# Tacho_StdTeile_panel.net
KiCad netlist of a schematic drawn in EAGLE
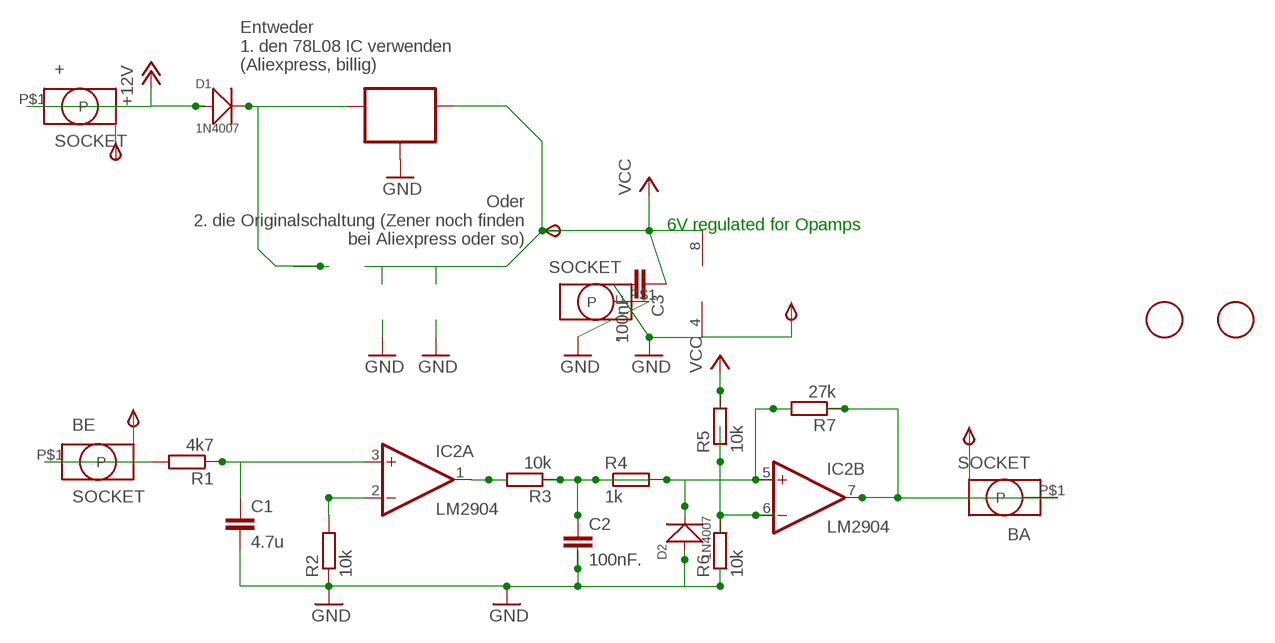
[diagram p0: schematic, sheet 1]
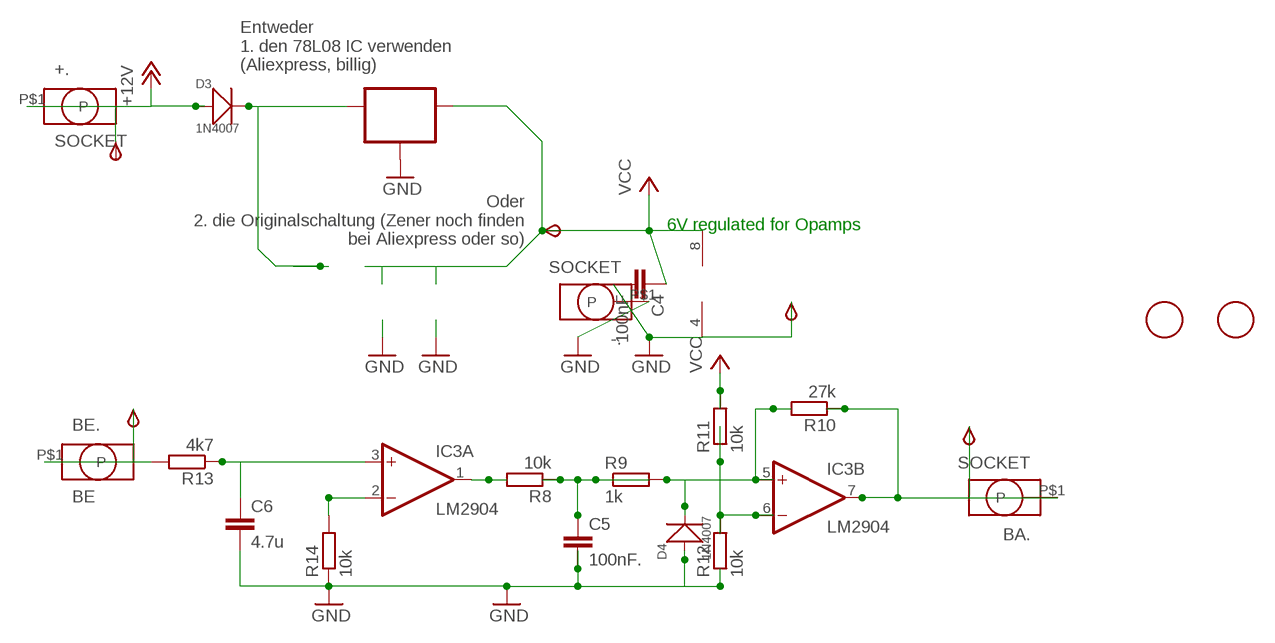
[diagram p1: schematic, sheet 2]
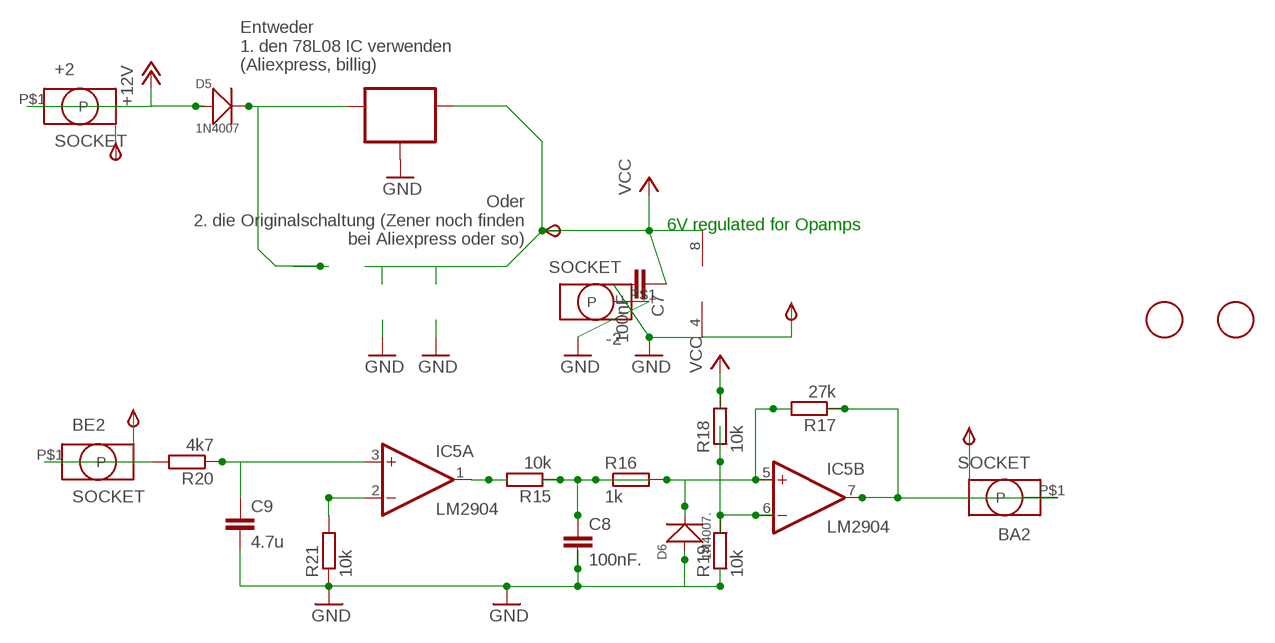
[diagram p2: schematic, sheet 3]
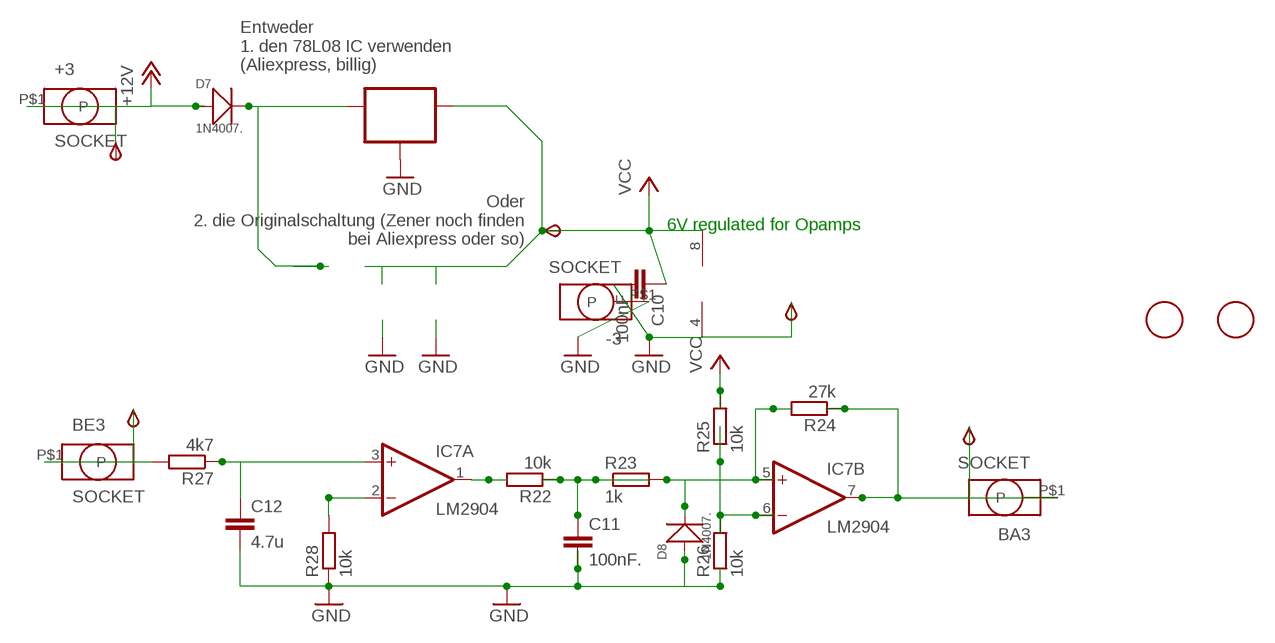
[diagram p3: schematic, sheet 4]
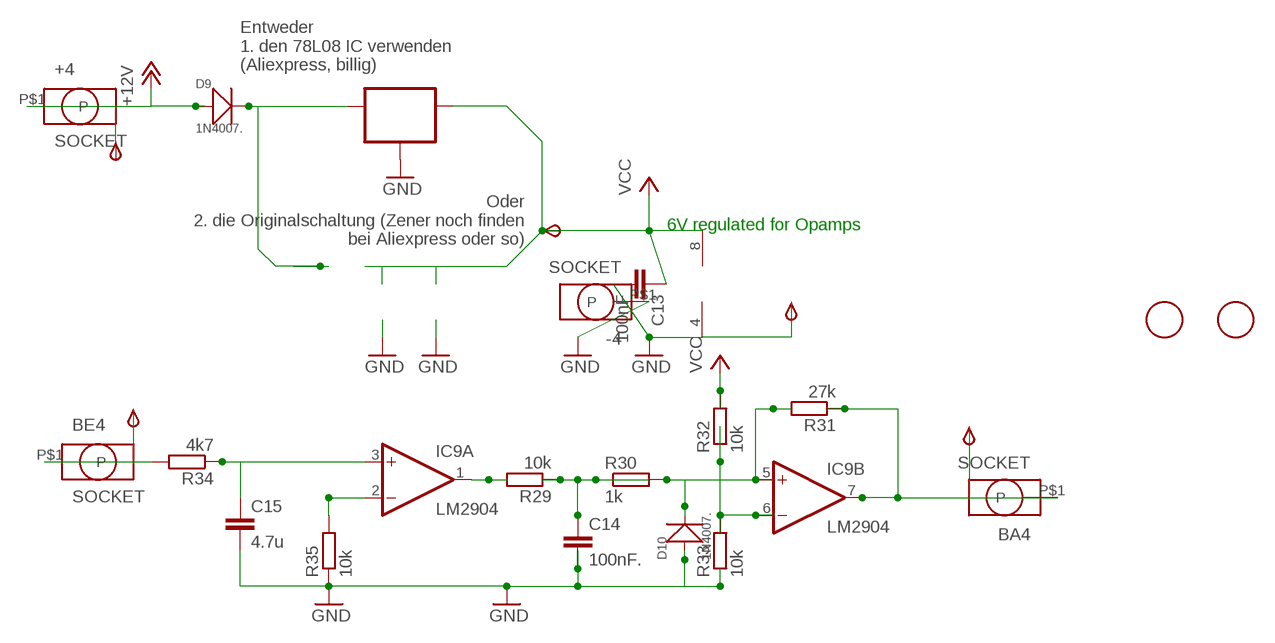
[diagram p4: schematic, sheet 5]
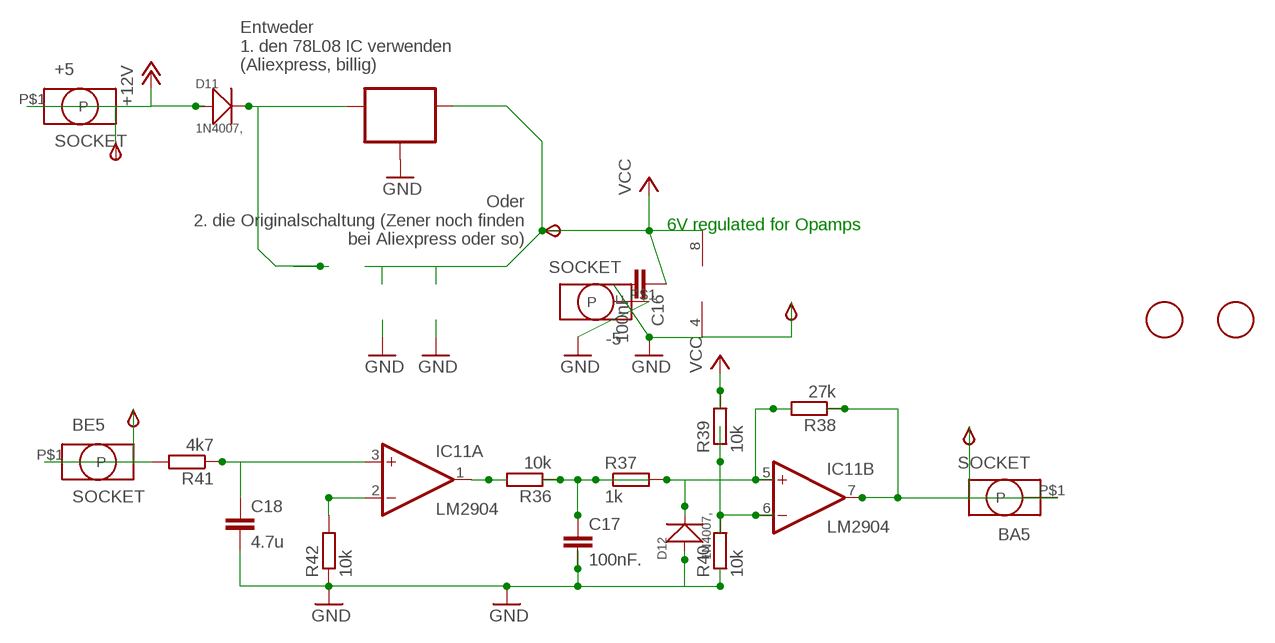
[diagram p5: schematic, sheet 6]
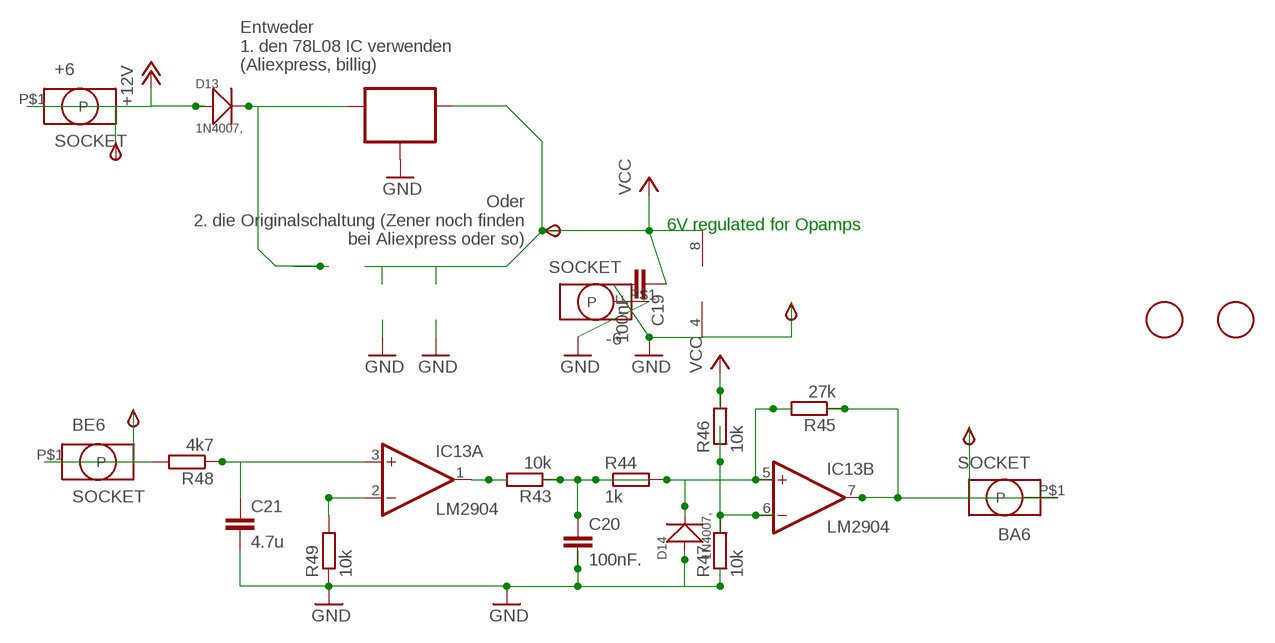
[diagram p6: schematic, sheet 7]
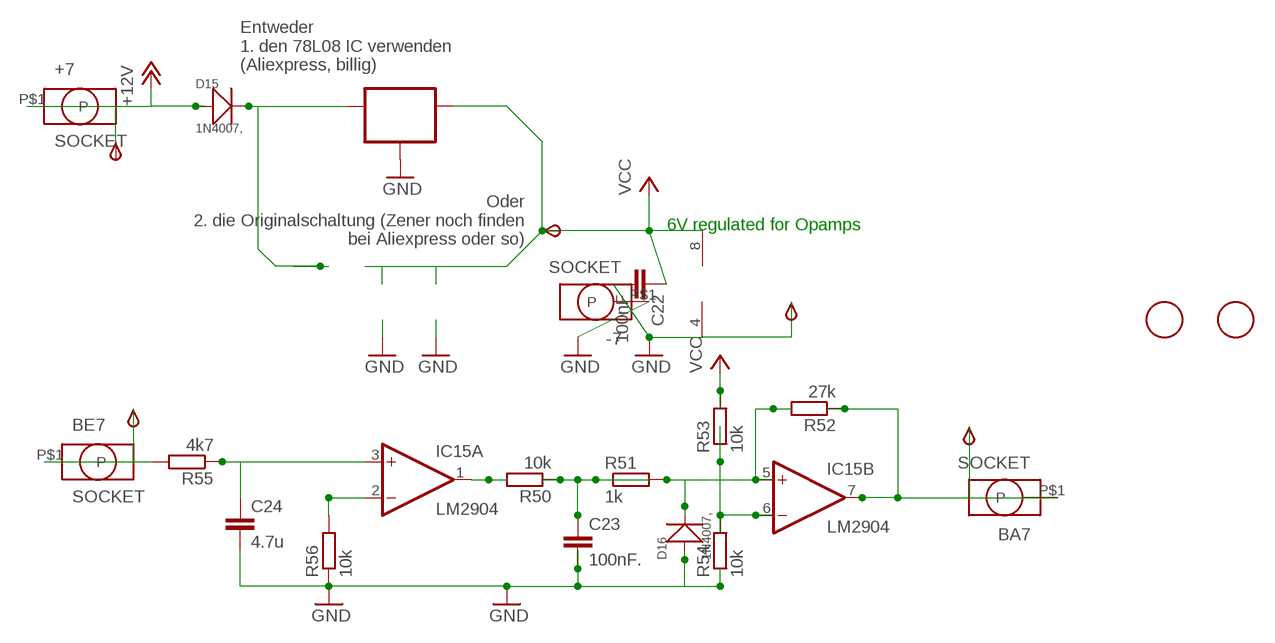
[diagram p7: schematic, sheet 8]

(export (version "E")
  (design (tool "Eeschema 10.0.6"))
  (components
    (comp (ref "+6")
      (value "SOCKET")
      (footprint "eagle-import:ID2.5MM")
      (libsource (lib "eagle-import") (part "SOCKET"))
    )
    (comp (ref "+12V6")
      (value "TPSB2.0")
      (footprint "eagle-import:B2.0")
      (libsource (lib "eagle-import") (part "TPSB2.0"))
    )
    (comp (ref "-6")
      (value "SOCKET")
      (footprint "eagle-import:ID2.5MM")
      (libsource (lib "eagle-import") (part "SOCKET"))
    )
    (comp (ref "6V6")
      (value "TPSB2.0")
      (footprint "eagle-import:B2.0")
      (libsource (lib "eagle-import") (part "TPSB2.0"))
    )
    (comp (ref "AUS6")
      (value "TPSB2.0")
      (footprint "eagle-import:B2.0")
      (libsource (lib "eagle-import") (part "TPSB2.0"))
    )
    (comp (ref "BA6")
      (value "SOCKET")
      (footprint "eagle-import:ID2.5MM")
      (libsource (lib "eagle-import") (part "SOCKET"))
    )
    (comp (ref "BE6")
      (value "SOCKET")
      (footprint "eagle-import:ID2.5MM")
      (libsource (lib "eagle-import") (part "SOCKET"))
    )
    (comp (ref "C19")
      (value "100nF")
      (footprint "eagle-import:C0805K")
      (libsource (lib "eagle-import") (part "C-EUC0805K"))
    )
    (comp (ref "C20")
      (value "100nF.")
      (footprint "eagle-import:C0805K")
      (libsource (lib "eagle-import") (part "C-EUC0805K"))
    )
    (comp (ref "C21")
      (value "4.7u")
      (footprint "eagle-import:C0805K")
      (libsource (lib "eagle-import") (part "C-EUC0805K"))
    )
    (comp (ref "D13")
      (value "1N4007,")
      (footprint "eagle-import:DO-214AC")
      (fields (field (name "MPN") "1N4007"))
      (libsource (lib "eagle-import") (part "DIODE-GEN-PURPOSE-1KV-1A(DO-214AC)"))
    )
    (comp (ref "D14")
      (value "1N4007,")
      (footprint "eagle-import:DO-214AC")
      (fields (field (name "MPN") "1N4007"))
      (libsource (lib "eagle-import") (part "DIODE-GEN-PURPOSE-1KV-1A(DO-214AC)"))
    )
    (comp (ref "EIN6")
      (value "TPSB2.0")
      (footprint "eagle-import:B2.0")
      (libsource (lib "eagle-import") (part "TPSB2.0"))
    )
    (comp (ref "FID13")
      (value "FIDUCIAL")
      (footprint "eagle-import:FIDUCIAL_1MM")
      (libsource (lib "eagle-import") (part "FIDUCIAL"))
    )
    (comp (ref "FID14")
      (value "FIDUCIAL")
      (footprint "eagle-import:FIDUCIAL_1MM")
      (libsource (lib "eagle-import") (part "FIDUCIAL"))
    )
    (comp (ref "GND55")
      (value "TPSB2.0")
      (footprint "eagle-import:B2.0")
      (libsource (lib "eagle-import") (part "TPSB2.0"))
    )
    (comp (ref "IC13")
      (value "LM2904")
      (footprint "eagle-import:SO08")
      (libsource (lib "eagle-import") (part "LM358D"))
    )
    (comp (ref "IC14")
      (value "78L06")
      (footprint "eagle-import:SOT89_ROUND")
      (libsource (lib "eagle-import") (part "78LXXSOT89_ROUND"))
    )
    (comp (ref "R43")
      (value "10k")
      (footprint "eagle-import:R0805")
      (libsource (lib "eagle-import") (part "R-EU_R0805"))
    )
    (comp (ref "R44")
      (value "1k")
      (footprint "eagle-import:R0805")
      (libsource (lib "eagle-import") (part "R-EU_R0805"))
    )
    (comp (ref "R45")
      (value "27k")
      (footprint "eagle-import:R0805")
      (libsource (lib "eagle-import") (part "R-EU_R0805"))
    )
    (comp (ref "R46")
      (value "10k")
      (footprint "eagle-import:R0805")
      (libsource (lib "eagle-import") (part "R-EU_R0805"))
    )
    (comp (ref "R47")
      (value "10k")
      (footprint "eagle-import:R0805")
      (libsource (lib "eagle-import") (part "R-EU_R0805"))
    )
    (comp (ref "R48")
      (value "4k7")
      (footprint "eagle-import:R0805")
      (libsource (lib "eagle-import") (part "R-EU_R0805"))
    )
    (comp (ref "R49")
      (value "10k")
      (footprint "eagle-import:R0805")
      (libsource (lib "eagle-import") (part "R-EU_R0805"))
    )
    (comp (ref "+.")
      (value "SOCKET")
      (footprint "eagle-import:ID2.5MM")
      (libsource (lib "eagle-import") (part "SOCKET"))
    )
    (comp (ref "+12V1")
      (value "TPSB2.0")
      (footprint "eagle-import:B2.0")
      (libsource (lib "eagle-import") (part "TPSB2.0"))
    )
    (comp (ref "-.")
      (value "SOCKET")
      (footprint "eagle-import:ID2.5MM")
      (libsource (lib "eagle-import") (part "SOCKET"))
    )
    (comp (ref "6V1")
      (value "TPSB2.0")
      (footprint "eagle-import:B2.0")
      (libsource (lib "eagle-import") (part "TPSB2.0"))
    )
    (comp (ref "AUS1")
      (value "TPSB2.0")
      (footprint "eagle-import:B2.0")
      (libsource (lib "eagle-import") (part "TPSB2.0"))
    )
    (comp (ref "BA.")
      (value "SOCKET")
      (footprint "eagle-import:ID2.5MM")
      (libsource (lib "eagle-import") (part "SOCKET"))
    )
    (comp (ref "BE.")
      (value "BE")
      (footprint "eagle-import:ID2.5MM")
      (libsource (lib "eagle-import") (part "SOCKET"))
    )
    (comp (ref "C4")
      (value "100nF")
      (footprint "eagle-import:C0805K")
      (libsource (lib "eagle-import") (part "C-EUC0805K"))
    )
    (comp (ref "C5")
      (value "100nF.")
      (footprint "eagle-import:C0805K")
      (libsource (lib "eagle-import") (part "C-EUC0805K"))
    )
    (comp (ref "C6")
      (value "4.7u")
      (footprint "eagle-import:C0805K")
      (libsource (lib "eagle-import") (part "C-EUC0805K"))
    )
    (comp (ref "D3")
      (value "1N4007")
      (footprint "eagle-import:DO-214AC")
      (libsource (lib "eagle-import") (part "DIODE-GEN-PURPOSE-1KV-1A(DO-214AC)"))
    )
    (comp (ref "D4")
      (value "1N4007")
      (footprint "eagle-import:DO-214AC")
      (libsource (lib "eagle-import") (part "DIODE-GEN-PURPOSE-1KV-1A(DO-214AC)"))
    )
    (comp (ref "EIN1")
      (value "TPSB2.0")
      (footprint "eagle-import:B2.0")
      (libsource (lib "eagle-import") (part "TPSB2.0"))
    )
    (comp (ref "FID3")
      (value "FIDUCIAL")
      (footprint "eagle-import:FIDUCIAL_1MM")
      (libsource (lib "eagle-import") (part "FIDUCIAL"))
    )
    (comp (ref "FID4")
      (value "FIDUCIAL")
      (footprint "eagle-import:FIDUCIAL_1MM")
      (libsource (lib "eagle-import") (part "FIDUCIAL"))
    )
    (comp (ref "GND12")
      (value "TPSB2.0")
      (footprint "eagle-import:B2.0")
      (libsource (lib "eagle-import") (part "TPSB2.0"))
    )
    (comp (ref "IC3")
      (value "LM2904")
      (footprint "eagle-import:SO08")
      (libsource (lib "eagle-import") (part "LM358D"))
    )
    (comp (ref "IC4")
      (value "78L06")
      (footprint "eagle-import:SOT89_ROUND")
      (libsource (lib "eagle-import") (part "78LXXSOT89_ROUND"))
    )
    (comp (ref "R8")
      (value "10k")
      (footprint "eagle-import:R0805")
      (libsource (lib "eagle-import") (part "R-EU_R0805"))
    )
    (comp (ref "R9")
      (value "1k")
      (footprint "eagle-import:R0805")
      (libsource (lib "eagle-import") (part "R-EU_R0805"))
    )
    (comp (ref "R10")
      (value "27k")
      (footprint "eagle-import:R0805")
      (libsource (lib "eagle-import") (part "R-EU_R0805"))
    )
    (comp (ref "R11")
      (value "10k")
      (footprint "eagle-import:R0805")
      (libsource (lib "eagle-import") (part "R-EU_R0805"))
    )
    (comp (ref "R12")
      (value "10k")
      (footprint "eagle-import:R0805")
      (libsource (lib "eagle-import") (part "R-EU_R0805"))
    )
    (comp (ref "R13")
      (value "4k7")
      (footprint "eagle-import:R0805")
      (libsource (lib "eagle-import") (part "R-EU_R0805"))
    )
    (comp (ref "R14")
      (value "10k")
      (footprint "eagle-import:R0805")
      (libsource (lib "eagle-import") (part "R-EU_R0805"))
    )
    (comp (ref "+3")
      (value "SOCKET")
      (footprint "eagle-import:ID2.5MM")
      (libsource (lib "eagle-import") (part "SOCKET"))
    )
    (comp (ref "+12V3")
      (value "TPSB2.0")
      (footprint "eagle-import:B2.0")
      (libsource (lib "eagle-import") (part "TPSB2.0"))
    )
    (comp (ref "-3")
      (value "SOCKET")
      (footprint "eagle-import:ID2.5MM")
      (libsource (lib "eagle-import") (part "SOCKET"))
    )
    (comp (ref "6V3")
      (value "TPSB2.0")
      (footprint "eagle-import:B2.0")
      (libsource (lib "eagle-import") (part "TPSB2.0"))
    )
    (comp (ref "AUS3")
      (value "TPSB2.0")
      (footprint "eagle-import:B2.0")
      (libsource (lib "eagle-import") (part "TPSB2.0"))
    )
    (comp (ref "BA3")
      (value "SOCKET")
      (footprint "eagle-import:ID2.5MM")
      (libsource (lib "eagle-import") (part "SOCKET"))
    )
    (comp (ref "BE3")
      (value "SOCKET")
      (footprint "eagle-import:ID2.5MM")
      (libsource (lib "eagle-import") (part "SOCKET"))
    )
    (comp (ref "C10")
      (value "100nF")
      (footprint "eagle-import:C0805K")
      (libsource (lib "eagle-import") (part "C-EUC0805K"))
    )
    (comp (ref "C11")
      (value "100nF.")
      (footprint "eagle-import:C0805K")
      (libsource (lib "eagle-import") (part "C-EUC0805K"))
    )
    (comp (ref "C12")
      (value "4.7u")
      (footprint "eagle-import:C0805K")
      (libsource (lib "eagle-import") (part "C-EUC0805K"))
    )
    (comp (ref "D7")
      (value "1N4007.")
      (footprint "eagle-import:DO-214AC")
      (fields (field (name "MPN") "1N4007"))
      (libsource (lib "eagle-import") (part "DIODE-GEN-PURPOSE-1KV-1A(DO-214AC)"))
    )
    (comp (ref "D8")
      (value "1N4007.")
      (footprint "eagle-import:DO-214AC")
      (fields (field (name "MPN") "1N4007"))
      (libsource (lib "eagle-import") (part "DIODE-GEN-PURPOSE-1KV-1A(DO-214AC)"))
    )
    (comp (ref "EIN3")
      (value "TPSB2.0")
      (footprint "eagle-import:B2.0")
      (libsource (lib "eagle-import") (part "TPSB2.0"))
    )
    (comp (ref "FID7")
      (value "FIDUCIAL")
      (footprint "eagle-import:FIDUCIAL_1MM")
      (libsource (lib "eagle-import") (part "FIDUCIAL"))
    )
    (comp (ref "FID8")
      (value "FIDUCIAL")
      (footprint "eagle-import:FIDUCIAL_1MM")
      (libsource (lib "eagle-import") (part "FIDUCIAL"))
    )
    (comp (ref "GND29")
      (value "TPSB2.0")
      (footprint "eagle-import:B2.0")
      (libsource (lib "eagle-import") (part "TPSB2.0"))
    )
    (comp (ref "IC7")
      (value "LM2904")
      (footprint "eagle-import:SO08")
      (libsource (lib "eagle-import") (part "LM358D"))
    )
    (comp (ref "IC8")
      (value "78L06")
      (footprint "eagle-import:SOT89_ROUND")
      (libsource (lib "eagle-import") (part "78LXXSOT89_ROUND"))
    )
    (comp (ref "R22")
      (value "10k")
      (footprint "eagle-import:R0805")
      (libsource (lib "eagle-import") (part "R-EU_R0805"))
    )
    (comp (ref "R23")
      (value "1k")
      (footprint "eagle-import:R0805")
      (libsource (lib "eagle-import") (part "R-EU_R0805"))
    )
    (comp (ref "R24")
      (value "27k")
      (footprint "eagle-import:R0805")
      (libsource (lib "eagle-import") (part "R-EU_R0805"))
    )
    (comp (ref "R25")
      (value "10k")
      (footprint "eagle-import:R0805")
      (libsource (lib "eagle-import") (part "R-EU_R0805"))
    )
    (comp (ref "R26")
      (value "10k")
      (footprint "eagle-import:R0805")
      (libsource (lib "eagle-import") (part "R-EU_R0805"))
    )
    (comp (ref "R27")
      (value "4k7")
      (footprint "eagle-import:R0805")
      (libsource (lib "eagle-import") (part "R-EU_R0805"))
    )
    (comp (ref "R28")
      (value "10k")
      (footprint "eagle-import:R0805")
      (libsource (lib "eagle-import") (part "R-EU_R0805"))
    )
    (comp (ref "+5")
      (value "SOCKET")
      (footprint "eagle-import:ID2.5MM")
      (libsource (lib "eagle-import") (part "SOCKET"))
    )
    (comp (ref "+12V5")
      (value "TPSB2.0")
      (footprint "eagle-import:B2.0")
      (libsource (lib "eagle-import") (part "TPSB2.0"))
    )
    (comp (ref "-5")
      (value "SOCKET")
      (footprint "eagle-import:ID2.5MM")
      (libsource (lib "eagle-import") (part "SOCKET"))
    )
    (comp (ref "6V5")
      (value "TPSB2.0")
      (footprint "eagle-import:B2.0")
      (libsource (lib "eagle-import") (part "TPSB2.0"))
    )
    (comp (ref "AUS5")
      (value "TPSB2.0")
      (footprint "eagle-import:B2.0")
      (libsource (lib "eagle-import") (part "TPSB2.0"))
    )
    (comp (ref "BA5")
      (value "SOCKET")
      (footprint "eagle-import:ID2.5MM")
      (libsource (lib "eagle-import") (part "SOCKET"))
    )
    (comp (ref "BE5")
      (value "SOCKET")
      (footprint "eagle-import:ID2.5MM")
      (libsource (lib "eagle-import") (part "SOCKET"))
    )
    (comp (ref "C16")
      (value "100nF")
      (footprint "eagle-import:C0805K")
      (libsource (lib "eagle-import") (part "C-EUC0805K"))
    )
    (comp (ref "C17")
      (value "100nF.")
      (footprint "eagle-import:C0805K")
      (libsource (lib "eagle-import") (part "C-EUC0805K"))
    )
    (comp (ref "C18")
      (value "4.7u")
      (footprint "eagle-import:C0805K")
      (libsource (lib "eagle-import") (part "C-EUC0805K"))
    )
    (comp (ref "D11")
      (value "1N4007,")
      (footprint "eagle-import:DO-214AC")
      (fields (field (name "MPN") "1N4007"))
      (libsource (lib "eagle-import") (part "DIODE-GEN-PURPOSE-1KV-1A(DO-214AC)"))
    )
    (comp (ref "D12")
      (value "1N4007,")
      (footprint "eagle-import:DO-214AC")
      (fields (field (name "MPN") "1N4007"))
      (libsource (lib "eagle-import") (part "DIODE-GEN-PURPOSE-1KV-1A(DO-214AC)"))
    )
    (comp (ref "EIN5")
      (value "TPSB2.0")
      (footprint "eagle-import:B2.0")
      (libsource (lib "eagle-import") (part "TPSB2.0"))
    )
    (comp (ref "FID11")
      (value "FIDUCIAL")
      (footprint "eagle-import:FIDUCIAL_1MM")
      (libsource (lib "eagle-import") (part "FIDUCIAL"))
    )
    (comp (ref "FID12")
      (value "FIDUCIAL")
      (footprint "eagle-import:FIDUCIAL_1MM")
      (libsource (lib "eagle-import") (part "FIDUCIAL"))
    )
    (comp (ref "GND47")
      (value "TPSB2.0")
      (footprint "eagle-import:B2.0")
      (libsource (lib "eagle-import") (part "TPSB2.0"))
    )
    (comp (ref "IC11")
      (value "LM2904")
      (footprint "eagle-import:SO08")
      (libsource (lib "eagle-import") (part "LM358D"))
    )
    (comp (ref "IC12")
      (value "78L06")
      (footprint "eagle-import:SOT89_ROUND")
      (libsource (lib "eagle-import") (part "78LXXSOT89_ROUND"))
    )
    (comp (ref "R36")
      (value "10k")
      (footprint "eagle-import:R0805")
      (libsource (lib "eagle-import") (part "R-EU_R0805"))
    )
    (comp (ref "R37")
      (value "1k")
      (footprint "eagle-import:R0805")
      (libsource (lib "eagle-import") (part "R-EU_R0805"))
    )
    (comp (ref "R38")
      (value "27k")
      (footprint "eagle-import:R0805")
      (libsource (lib "eagle-import") (part "R-EU_R0805"))
    )
    (comp (ref "R39")
      (value "10k")
      (footprint "eagle-import:R0805")
      (libsource (lib "eagle-import") (part "R-EU_R0805"))
    )
    (comp (ref "R40")
      (value "10k")
      (footprint "eagle-import:R0805")
      (libsource (lib "eagle-import") (part "R-EU_R0805"))
    )
    (comp (ref "R41")
      (value "4k7")
      (footprint "eagle-import:R0805")
      (libsource (lib "eagle-import") (part "R-EU_R0805"))
    )
    (comp (ref "R42")
      (value "10k")
      (footprint "eagle-import:R0805")
      (libsource (lib "eagle-import") (part "R-EU_R0805"))
    )
    (comp (ref "+2")
      (value "SOCKET")
      (footprint "eagle-import:ID2.5MM")
      (libsource (lib "eagle-import") (part "SOCKET"))
    )
    (comp (ref "+12V2")
      (value "TPSB2.0")
      (footprint "eagle-import:B2.0")
      (libsource (lib "eagle-import") (part "TPSB2.0"))
    )
    (comp (ref "-2")
      (value "SOCKET")
      (footprint "eagle-import:ID2.5MM")
      (libsource (lib "eagle-import") (part "SOCKET"))
    )
    (comp (ref "6V2")
      (value "TPSB2.0")
      (footprint "eagle-import:B2.0")
      (libsource (lib "eagle-import") (part "TPSB2.0"))
    )
    (comp (ref "AUS2")
      (value "TPSB2.0")
      (footprint "eagle-import:B2.0")
      (libsource (lib "eagle-import") (part "TPSB2.0"))
    )
    (comp (ref "BA2")
      (value "SOCKET")
      (footprint "eagle-import:ID2.5MM")
      (libsource (lib "eagle-import") (part "SOCKET"))
    )
    (comp (ref "BE2")
      (value "SOCKET")
      (footprint "eagle-import:ID2.5MM")
      (libsource (lib "eagle-import") (part "SOCKET"))
    )
    (comp (ref "C7")
      (value "100nF")
      (footprint "eagle-import:C0805K")
      (libsource (lib "eagle-import") (part "C-EUC0805K"))
    )
    (comp (ref "C8")
      (value "100nF.")
      (footprint "eagle-import:C0805K")
      (libsource (lib "eagle-import") (part "C-EUC0805K"))
    )
    (comp (ref "C9")
      (value "4.7u")
      (footprint "eagle-import:C0805K")
      (libsource (lib "eagle-import") (part "C-EUC0805K"))
    )
    (comp (ref "D5")
      (value "1N4007")
      (footprint "eagle-import:DO-214AC")
      (libsource (lib "eagle-import") (part "DIODE-GEN-PURPOSE-1KV-1A(DO-214AC)"))
    )
    (comp (ref "D6")
      (value "1N4007.")
      (footprint "eagle-import:DO-214AC")
      (fields (field (name "MPN") "1N4007"))
      (libsource (lib "eagle-import") (part "DIODE-GEN-PURPOSE-1KV-1A(DO-214AC)"))
    )
    (comp (ref "EIN2")
      (value "TPSB2.0")
      (footprint "eagle-import:B2.0")
      (libsource (lib "eagle-import") (part "TPSB2.0"))
    )
    (comp (ref "FID5")
      (value "FIDUCIAL")
      (footprint "eagle-import:FIDUCIAL_1MM")
      (libsource (lib "eagle-import") (part "FIDUCIAL"))
    )
    (comp (ref "FID6")
      (value "FIDUCIAL")
      (footprint "eagle-import:FIDUCIAL_1MM")
      (libsource (lib "eagle-import") (part "FIDUCIAL"))
    )
    (comp (ref "GND20")
      (value "TPSB2.0")
      (footprint "eagle-import:B2.0")
      (libsource (lib "eagle-import") (part "TPSB2.0"))
    )
    (comp (ref "IC5")
      (value "LM2904")
      (footprint "eagle-import:SO08")
      (libsource (lib "eagle-import") (part "LM358D"))
    )
    (comp (ref "IC6")
      (value "78L06")
      (footprint "eagle-import:SOT89_ROUND")
      (libsource (lib "eagle-import") (part "78LXXSOT89_ROUND"))
    )
    (comp (ref "R15")
      (value "10k")
      (footprint "eagle-import:R0805")
      (libsource (lib "eagle-import") (part "R-EU_R0805"))
    )
    (comp (ref "R16")
      (value "1k")
      (footprint "eagle-import:R0805")
      (libsource (lib "eagle-import") (part "R-EU_R0805"))
    )
    (comp (ref "R17")
      (value "27k")
      (footprint "eagle-import:R0805")
      (libsource (lib "eagle-import") (part "R-EU_R0805"))
    )
    (comp (ref "R18")
      (value "10k")
      (footprint "eagle-import:R0805")
      (libsource (lib "eagle-import") (part "R-EU_R0805"))
    )
    (comp (ref "R19")
      (value "10k")
      (footprint "eagle-import:R0805")
      (libsource (lib "eagle-import") (part "R-EU_R0805"))
    )
    (comp (ref "R20")
      (value "4k7")
      (footprint "eagle-import:R0805")
      (libsource (lib "eagle-import") (part "R-EU_R0805"))
    )
    (comp (ref "R21")
      (value "10k")
      (footprint "eagle-import:R0805")
      (libsource (lib "eagle-import") (part "R-EU_R0805"))
    )
    (comp (ref "+7")
      (value "SOCKET")
      (footprint "eagle-import:ID2.5MM")
      (libsource (lib "eagle-import") (part "SOCKET"))
    )
    (comp (ref "+12V7")
      (value "TPSB2.0")
      (footprint "eagle-import:B2.0")
      (libsource (lib "eagle-import") (part "TPSB2.0"))
    )
    (comp (ref "-7")
      (value "SOCKET")
      (footprint "eagle-import:ID2.5MM")
      (libsource (lib "eagle-import") (part "SOCKET"))
    )
    (comp (ref "6V7")
      (value "TPSB2.0")
      (footprint "eagle-import:B2.0")
      (libsource (lib "eagle-import") (part "TPSB2.0"))
    )
    (comp (ref "AUS7")
      (value "TPSB2.0")
      (footprint "eagle-import:B2.0")
      (libsource (lib "eagle-import") (part "TPSB2.0"))
    )
    (comp (ref "BA7")
      (value "SOCKET")
      (footprint "eagle-import:ID2.5MM")
      (libsource (lib "eagle-import") (part "SOCKET"))
    )
    (comp (ref "BE7")
      (value "SOCKET")
      (footprint "eagle-import:ID2.5MM")
      (libsource (lib "eagle-import") (part "SOCKET"))
    )
    (comp (ref "C22")
      (value "100nF")
      (footprint "eagle-import:C0805K")
      (libsource (lib "eagle-import") (part "C-EUC0805K"))
    )
    (comp (ref "C23")
      (value "100nF.")
      (footprint "eagle-import:C0805K")
      (libsource (lib "eagle-import") (part "C-EUC0805K"))
    )
    (comp (ref "C24")
      (value "4.7u")
      (footprint "eagle-import:C0805K")
      (libsource (lib "eagle-import") (part "C-EUC0805K"))
    )
    (comp (ref "D15")
      (value "1N4007,")
      (footprint "eagle-import:DO-214AC")
      (fields (field (name "MPN") "1N4007"))
      (libsource (lib "eagle-import") (part "DIODE-GEN-PURPOSE-1KV-1A(DO-214AC)"))
    )
    (comp (ref "D16")
      (value "1N4007,")
      (footprint "eagle-import:DO-214AC")
      (fields (field (name "MPN") "1N4007"))
      (libsource (lib "eagle-import") (part "DIODE-GEN-PURPOSE-1KV-1A(DO-214AC)"))
    )
    (comp (ref "EIN7")
      (value "TPSB2.0")
      (footprint "eagle-import:B2.0")
      (libsource (lib "eagle-import") (part "TPSB2.0"))
    )
    (comp (ref "FID1")
      (value "FIDUCIAL")
      (footprint "eagle-import:FIDUCIAL_1MM")
      (libsource (lib "eagle-import") (part "FIDUCIAL"))
    )
    (comp (ref "FID19")
      (value "FIDUCIAL")
      (footprint "eagle-import:FIDUCIAL_1MM")
      (libsource (lib "eagle-import") (part "FIDUCIAL"))
    )
    (comp (ref "GND63")
      (value "TPSB2.0")
      (footprint "eagle-import:B2.0")
      (libsource (lib "eagle-import") (part "TPSB2.0"))
    )
    (comp (ref "IC15")
      (value "LM2904")
      (footprint "eagle-import:SO08")
      (libsource (lib "eagle-import") (part "LM358D"))
    )
    (comp (ref "IC16")
      (value "78L06")
      (footprint "eagle-import:SOT89_ROUND")
      (libsource (lib "eagle-import") (part "78LXXSOT89_ROUND"))
    )
    (comp (ref "R50")
      (value "10k")
      (footprint "eagle-import:R0805")
      (libsource (lib "eagle-import") (part "R-EU_R0805"))
    )
    (comp (ref "R51")
      (value "1k")
      (footprint "eagle-import:R0805")
      (libsource (lib "eagle-import") (part "R-EU_R0805"))
    )
    (comp (ref "R52")
      (value "27k")
      (footprint "eagle-import:R0805")
      (libsource (lib "eagle-import") (part "R-EU_R0805"))
    )
    (comp (ref "R53")
      (value "10k")
      (footprint "eagle-import:R0805")
      (libsource (lib "eagle-import") (part "R-EU_R0805"))
    )
    (comp (ref "R54")
      (value "10k")
      (footprint "eagle-import:R0805")
      (libsource (lib "eagle-import") (part "R-EU_R0805"))
    )
    (comp (ref "R55")
      (value "4k7")
      (footprint "eagle-import:R0805")
      (libsource (lib "eagle-import") (part "R-EU_R0805"))
    )
    (comp (ref "R56")
      (value "10k")
      (footprint "eagle-import:R0805")
      (libsource (lib "eagle-import") (part "R-EU_R0805"))
    )
    (comp (ref "+4")
      (value "SOCKET")
      (footprint "eagle-import:ID2.5MM")
      (libsource (lib "eagle-import") (part "SOCKET"))
    )
    (comp (ref "+12V4")
      (value "TPSB2.0")
      (footprint "eagle-import:B2.0")
      (libsource (lib "eagle-import") (part "TPSB2.0"))
    )
    (comp (ref "-4")
      (value "SOCKET")
      (footprint "eagle-import:ID2.5MM")
      (libsource (lib "eagle-import") (part "SOCKET"))
    )
    (comp (ref "6V4")
      (value "TPSB2.0")
      (footprint "eagle-import:B2.0")
      (libsource (lib "eagle-import") (part "TPSB2.0"))
    )
    (comp (ref "AUS4")
      (value "TPSB2.0")
      (footprint "eagle-import:B2.0")
      (libsource (lib "eagle-import") (part "TPSB2.0"))
    )
    (comp (ref "BA4")
      (value "SOCKET")
      (footprint "eagle-import:ID2.5MM")
      (libsource (lib "eagle-import") (part "SOCKET"))
    )
    (comp (ref "BE4")
      (value "SOCKET")
      (footprint "eagle-import:ID2.5MM")
      (libsource (lib "eagle-import") (part "SOCKET"))
    )
    (comp (ref "C13")
      (value "100nF")
      (footprint "eagle-import:C0805K")
      (libsource (lib "eagle-import") (part "C-EUC0805K"))
    )
    (comp (ref "C14")
      (value "100nF.")
      (footprint "eagle-import:C0805K")
      (libsource (lib "eagle-import") (part "C-EUC0805K"))
    )
    (comp (ref "C15")
      (value "4.7u")
      (footprint "eagle-import:C0805K")
      (libsource (lib "eagle-import") (part "C-EUC0805K"))
    )
    (comp (ref "D9")
      (value "1N4007.")
      (footprint "eagle-import:DO-214AC")
      (fields (field (name "MPN") "1N4007"))
      (libsource (lib "eagle-import") (part "DIODE-GEN-PURPOSE-1KV-1A(DO-214AC)"))
    )
    (comp (ref "D10")
      (value "1N4007.")
      (footprint "eagle-import:DO-214AC")
      (fields (field (name "MPN") "1N4007"))
      (libsource (lib "eagle-import") (part "DIODE-GEN-PURPOSE-1KV-1A(DO-214AC)"))
    )
    (comp (ref "EIN4")
      (value "TPSB2.0")
      (footprint "eagle-import:B2.0")
      (libsource (lib "eagle-import") (part "TPSB2.0"))
    )
    (comp (ref "FID9")
      (value "FIDUCIAL")
      (footprint "eagle-import:FIDUCIAL_1MM")
      (libsource (lib "eagle-import") (part "FIDUCIAL"))
    )
    (comp (ref "FID10")
      (value "FIDUCIAL")
      (footprint "eagle-import:FIDUCIAL_1MM")
      (libsource (lib "eagle-import") (part "FIDUCIAL"))
    )
    (comp (ref "GND39")
      (value "TPSB2.0")
      (footprint "eagle-import:B2.0")
      (libsource (lib "eagle-import") (part "TPSB2.0"))
    )
    (comp (ref "IC9")
      (value "LM2904")
      (footprint "eagle-import:SO08")
      (libsource (lib "eagle-import") (part "LM358D"))
    )
    (comp (ref "IC10")
      (value "78L06")
      (footprint "eagle-import:SOT89_ROUND")
      (libsource (lib "eagle-import") (part "78LXXSOT89_ROUND"))
    )
    (comp (ref "R29")
      (value "10k")
      (footprint "eagle-import:R0805")
      (libsource (lib "eagle-import") (part "R-EU_R0805"))
    )
    (comp (ref "R30")
      (value "1k")
      (footprint "eagle-import:R0805")
      (libsource (lib "eagle-import") (part "R-EU_R0805"))
    )
    (comp (ref "R31")
      (value "27k")
      (footprint "eagle-import:R0805")
      (libsource (lib "eagle-import") (part "R-EU_R0805"))
    )
    (comp (ref "R32")
      (value "10k")
      (footprint "eagle-import:R0805")
      (libsource (lib "eagle-import") (part "R-EU_R0805"))
    )
    (comp (ref "R33")
      (value "10k")
      (footprint "eagle-import:R0805")
      (libsource (lib "eagle-import") (part "R-EU_R0805"))
    )
    (comp (ref "R34")
      (value "4k7")
      (footprint "eagle-import:R0805")
      (libsource (lib "eagle-import") (part "R-EU_R0805"))
    )
    (comp (ref "R35")
      (value "10k")
      (footprint "eagle-import:R0805")
      (libsource (lib "eagle-import") (part "R-EU_R0805"))
    )
    (comp (ref "+")
      (value "SOCKET")
      (footprint "eagle-import:ID2.5MM")
      (libsource (lib "eagle-import") (part "SOCKET"))
    )
    (comp (ref "+12V")
      (value "TPSB2.0")
      (footprint "eagle-import:B2.0")
      (libsource (lib "eagle-import") (part "TPSB2.0"))
    )
    (comp (ref "-")
      (value "SOCKET")
      (footprint "eagle-import:ID2.5MM")
      (libsource (lib "eagle-import") (part "SOCKET"))
    )
    (comp (ref "6V")
      (value "TPSB2.0")
      (footprint "eagle-import:B2.0")
      (libsource (lib "eagle-import") (part "TPSB2.0"))
    )
    (comp (ref "AUS")
      (value "TPSB2.0")
      (footprint "eagle-import:B2.0")
      (libsource (lib "eagle-import") (part "TPSB2.0"))
    )
    (comp (ref "BA")
      (value "SOCKET")
      (footprint "eagle-import:ID2.5MM")
      (libsource (lib "eagle-import") (part "SOCKET"))
    )
    (comp (ref "BE")
      (value "SOCKET")
      (footprint "eagle-import:ID2.5MM")
      (libsource (lib "eagle-import") (part "SOCKET"))
    )
    (comp (ref "C1")
      (value "4.7u")
      (footprint "eagle-import:C0805K")
      (libsource (lib "eagle-import") (part "C-EUC0805K"))
    )
    (comp (ref "C2")
      (value "100nF.")
      (footprint "eagle-import:C0805K")
      (libsource (lib "eagle-import") (part "C-EUC0805K"))
    )
    (comp (ref "C3")
      (value "100nF")
      (footprint "eagle-import:C0805K")
      (libsource (lib "eagle-import") (part "C-EUC0805K"))
    )
    (comp (ref "D1")
      (value "1N4007")
      (footprint "eagle-import:DO-214AC")
      (libsource (lib "eagle-import") (part "DIODE-GEN-PURPOSE-1KV-1A(DO-214AC)"))
    )
    (comp (ref "D2")
      (value "1N4007")
      (footprint "eagle-import:DO-214AC")
      (libsource (lib "eagle-import") (part "DIODE-GEN-PURPOSE-1KV-1A(DO-214AC)"))
    )
    (comp (ref "EIN")
      (value "TPSB2.0")
      (footprint "eagle-import:B2.0")
      (libsource (lib "eagle-import") (part "TPSB2.0"))
    )
    (comp (ref "FID2")
      (value "FIDUCIAL")
      (footprint "eagle-import:FIDUCIAL_1MM")
      (libsource (lib "eagle-import") (part "FIDUCIAL"))
    )
    (comp (ref "FID20")
      (value "FIDUCIAL")
      (footprint "eagle-import:FIDUCIAL_1MM")
      (libsource (lib "eagle-import") (part "FIDUCIAL"))
    )
    (comp (ref "GND")
      (value "TPSB2.0")
      (footprint "eagle-import:B2.0")
      (libsource (lib "eagle-import") (part "TPSB2.0"))
    )
    (comp (ref "IC1")
      (value "78L06")
      (footprint "eagle-import:SOT89_ROUND")
      (libsource (lib "eagle-import") (part "78LXXSOT89_ROUND"))
    )
    (comp (ref "IC2")
      (value "LM2904")
      (footprint "eagle-import:SO08")
      (libsource (lib "eagle-import") (part "LM358D"))
    )
    (comp (ref "R1")
      (value "4k7")
      (footprint "eagle-import:R0805")
      (libsource (lib "eagle-import") (part "R-EU_R0805"))
    )
    (comp (ref "R2")
      (value "10k")
      (footprint "eagle-import:R0805")
      (libsource (lib "eagle-import") (part "R-EU_R0805"))
    )
    (comp (ref "R3")
      (value "10k")
      (footprint "eagle-import:R0805")
      (libsource (lib "eagle-import") (part "R-EU_R0805"))
    )
    (comp (ref "R4")
      (value "1k")
      (footprint "eagle-import:R0805")
      (libsource (lib "eagle-import") (part "R-EU_R0805"))
    )
    (comp (ref "R5")
      (value "10k")
      (footprint "eagle-import:R0805")
      (libsource (lib "eagle-import") (part "R-EU_R0805"))
    )
    (comp (ref "R6")
      (value "10k")
      (footprint "eagle-import:R0805")
      (libsource (lib "eagle-import") (part "R-EU_R0805"))
    )
    (comp (ref "R7")
      (value "27k")
      (footprint "eagle-import:R0805")
      (libsource (lib "eagle-import") (part "R-EU_R0805"))
    )
  )
  (nets
    (net (code "1") (name "+12V") (class "Default")
      (node (ref "+") (pin "P$1") (pinfunction "P_P$1") (pintype "bidirectional"))
      (node (ref "+.") (pin "P$1") (pinfunction "P_P$1") (pintype "bidirectional"))
      (node (ref "+12V") (pin "TP") (pinfunction "PP_TP") (pintype "input"))
      (node (ref "+12V1") (pin "TP") (pinfunction "PP_TP") (pintype "input"))
      (node (ref "+12V2") (pin "TP") (pinfunction "PP_TP") (pintype "input"))
      (node (ref "+12V3") (pin "TP") (pinfunction "PP_TP") (pintype "input"))
      (node (ref "+12V4") (pin "TP") (pinfunction "PP_TP") (pintype "input"))
      (node (ref "+12V5") (pin "TP") (pinfunction "PP_TP") (pintype "input"))
      (node (ref "+12V6") (pin "TP") (pinfunction "PP_TP") (pintype "input"))
      (node (ref "+12V7") (pin "TP") (pinfunction "PP_TP") (pintype "input"))
      (node (ref "+2") (pin "P$1") (pinfunction "P_P$1") (pintype "bidirectional"))
      (node (ref "+3") (pin "P$1") (pinfunction "P_P$1") (pintype "bidirectional"))
      (node (ref "+4") (pin "P$1") (pinfunction "P_P$1") (pintype "bidirectional"))
      (node (ref "+5") (pin "P$1") (pinfunction "P_P$1") (pintype "bidirectional"))
      (node (ref "+6") (pin "P$1") (pinfunction "P_P$1") (pintype "bidirectional"))
      (node (ref "+7") (pin "P$1") (pinfunction "P_P$1") (pintype "bidirectional"))
      (node (ref "D1") (pin "1") (pinfunction "+_1") (pintype "passive"))
      (node (ref "D11") (pin "1") (pinfunction "+_1") (pintype "passive"))
      (node (ref "D13") (pin "1") (pinfunction "+_1") (pintype "passive"))
      (node (ref "D15") (pin "1") (pinfunction "+_1") (pintype "passive"))
      (node (ref "D3") (pin "1") (pinfunction "+_1") (pintype "passive"))
      (node (ref "D5") (pin "1") (pinfunction "+_1") (pintype "passive"))
      (node (ref "D7") (pin "1") (pinfunction "+_1") (pintype "passive"))
      (node (ref "D9") (pin "1") (pinfunction "+_1") (pintype "passive"))
    )
    (net (code "2") (name "GND") (class "Default")
      (node (ref "-") (pin "P$1") (pinfunction "P_P$1") (pintype "bidirectional"))
      (node (ref "-.") (pin "P$1") (pinfunction "P_P$1") (pintype "bidirectional"))
      (node (ref "-2") (pin "P$1") (pinfunction "P_P$1") (pintype "bidirectional"))
      (node (ref "-3") (pin "P$1") (pinfunction "P_P$1") (pintype "bidirectional"))
      (node (ref "-4") (pin "P$1") (pinfunction "P_P$1") (pintype "bidirectional"))
      (node (ref "-5") (pin "P$1") (pinfunction "P_P$1") (pintype "bidirectional"))
      (node (ref "-6") (pin "P$1") (pinfunction "P_P$1") (pintype "bidirectional"))
      (node (ref "-7") (pin "P$1") (pinfunction "P_P$1") (pintype "bidirectional"))
      (node (ref "C1") (pin "2") (pinfunction "2_2") (pintype "passive"))
      (node (ref "C10") (pin "2") (pinfunction "2_2") (pintype "passive"))
      (node (ref "C11") (pin "2") (pinfunction "2_2") (pintype "passive"))
      (node (ref "C12") (pin "2") (pinfunction "2_2") (pintype "passive"))
      (node (ref "C13") (pin "2") (pinfunction "2_2") (pintype "passive"))
      (node (ref "C14") (pin "2") (pinfunction "2_2") (pintype "passive"))
      (node (ref "C15") (pin "2") (pinfunction "2_2") (pintype "passive"))
      (node (ref "C16") (pin "2") (pinfunction "2_2") (pintype "passive"))
      (node (ref "C17") (pin "2") (pinfunction "2_2") (pintype "passive"))
      (node (ref "C18") (pin "2") (pinfunction "2_2") (pintype "passive"))
      (node (ref "C19") (pin "2") (pinfunction "2_2") (pintype "passive"))
      (node (ref "C2") (pin "2") (pinfunction "2_2") (pintype "passive"))
      (node (ref "C20") (pin "2") (pinfunction "2_2") (pintype "passive"))
      (node (ref "C21") (pin "2") (pinfunction "2_2") (pintype "passive"))
      (node (ref "C22") (pin "2") (pinfunction "2_2") (pintype "passive"))
      (node (ref "C23") (pin "2") (pinfunction "2_2") (pintype "passive"))
      (node (ref "C24") (pin "2") (pinfunction "2_2") (pintype "passive"))
      (node (ref "C3") (pin "2") (pinfunction "2_2") (pintype "passive"))
      (node (ref "C4") (pin "2") (pinfunction "2_2") (pintype "passive"))
      (node (ref "C5") (pin "2") (pinfunction "2_2") (pintype "passive"))
      (node (ref "C6") (pin "2") (pinfunction "2_2") (pintype "passive"))
      (node (ref "C7") (pin "2") (pinfunction "2_2") (pintype "passive"))
      (node (ref "C8") (pin "2") (pinfunction "2_2") (pintype "passive"))
      (node (ref "C9") (pin "2") (pinfunction "2_2") (pintype "passive"))
      (node (ref "D10") (pin "1") (pinfunction "+_1") (pintype "passive"))
      (node (ref "D12") (pin "1") (pinfunction "+_1") (pintype "passive"))
      (node (ref "D14") (pin "1") (pinfunction "+_1") (pintype "passive"))
      (node (ref "D16") (pin "1") (pinfunction "+_1") (pintype "passive"))
      (node (ref "D2") (pin "1") (pinfunction "+_1") (pintype "passive"))
      (node (ref "D4") (pin "1") (pinfunction "+_1") (pintype "passive"))
      (node (ref "D6") (pin "1") (pinfunction "+_1") (pintype "passive"))
      (node (ref "D8") (pin "1") (pinfunction "+_1") (pintype "passive"))
      (node (ref "GND") (pin "TP") (pinfunction "PP_TP") (pintype "input"))
      (node (ref "GND12") (pin "TP") (pinfunction "PP_TP") (pintype "input"))
      (node (ref "GND20") (pin "TP") (pinfunction "PP_TP") (pintype "input"))
      (node (ref "GND29") (pin "TP") (pinfunction "PP_TP") (pintype "input"))
      (node (ref "GND39") (pin "TP") (pinfunction "PP_TP") (pintype "input"))
      (node (ref "GND47") (pin "TP") (pinfunction "PP_TP") (pintype "input"))
      (node (ref "GND55") (pin "TP") (pinfunction "PP_TP") (pintype "input"))
      (node (ref "GND63") (pin "TP") (pinfunction "PP_TP") (pintype "input"))
      (node (ref "IC1") (pin "2") (pinfunction "GND_2") (pintype "input"))
      (node (ref "IC1") (pin "2@1") (pinfunction "GND_2@1") (pintype "input"))
      (node (ref "IC10") (pin "2") (pinfunction "GND_2") (pintype "input"))
      (node (ref "IC10") (pin "2@1") (pinfunction "GND_2@1") (pintype "input"))
      (node (ref "IC11") (pin "4") (pinfunction "V-_4") (pintype "power_in"))
      (node (ref "IC12") (pin "2") (pinfunction "GND_2") (pintype "input"))
      (node (ref "IC12") (pin "2@1") (pinfunction "GND_2@1") (pintype "input"))
      (node (ref "IC13") (pin "4") (pinfunction "V-_4") (pintype "power_in"))
      (node (ref "IC14") (pin "2") (pinfunction "GND_2") (pintype "input"))
      (node (ref "IC14") (pin "2@1") (pinfunction "GND_2@1") (pintype "input"))
      (node (ref "IC15") (pin "4") (pinfunction "V-_4") (pintype "power_in"))
      (node (ref "IC16") (pin "2") (pinfunction "GND_2") (pintype "input"))
      (node (ref "IC16") (pin "2@1") (pinfunction "GND_2@1") (pintype "input"))
      (node (ref "IC2") (pin "4") (pinfunction "V-_4") (pintype "power_in"))
      (node (ref "IC3") (pin "4") (pinfunction "V-_4") (pintype "power_in"))
      (node (ref "IC4") (pin "2") (pinfunction "GND_2") (pintype "input"))
      (node (ref "IC4") (pin "2@1") (pinfunction "GND_2@1") (pintype "input"))
      (node (ref "IC5") (pin "4") (pinfunction "V-_4") (pintype "power_in"))
      (node (ref "IC6") (pin "2") (pinfunction "GND_2") (pintype "input"))
      (node (ref "IC6") (pin "2@1") (pinfunction "GND_2@1") (pintype "input"))
      (node (ref "IC7") (pin "4") (pinfunction "V-_4") (pintype "power_in"))
      (node (ref "IC8") (pin "2") (pinfunction "GND_2") (pintype "input"))
      (node (ref "IC8") (pin "2@1") (pinfunction "GND_2@1") (pintype "input"))
      (node (ref "IC9") (pin "4") (pinfunction "V-_4") (pintype "power_in"))
      (node (ref "R12") (pin "1") (pinfunction "1_1") (pintype "passive"))
      (node (ref "R14") (pin "1") (pinfunction "1_1") (pintype "passive"))
      (node (ref "R19") (pin "1") (pinfunction "1_1") (pintype "passive"))
      (node (ref "R2") (pin "1") (pinfunction "1_1") (pintype "passive"))
      (node (ref "R21") (pin "1") (pinfunction "1_1") (pintype "passive"))
      (node (ref "R26") (pin "1") (pinfunction "1_1") (pintype "passive"))
      (node (ref "R28") (pin "1") (pinfunction "1_1") (pintype "passive"))
      (node (ref "R33") (pin "1") (pinfunction "1_1") (pintype "passive"))
      (node (ref "R35") (pin "1") (pinfunction "1_1") (pintype "passive"))
      (node (ref "R40") (pin "1") (pinfunction "1_1") (pintype "passive"))
      (node (ref "R42") (pin "1") (pinfunction "1_1") (pintype "passive"))
      (node (ref "R47") (pin "1") (pinfunction "1_1") (pintype "passive"))
      (node (ref "R49") (pin "1") (pinfunction "1_1") (pintype "passive"))
      (node (ref "R54") (pin "1") (pinfunction "1_1") (pintype "passive"))
      (node (ref "R56") (pin "1") (pinfunction "1_1") (pintype "passive"))
      (node (ref "R6") (pin "1") (pinfunction "1_1") (pintype "passive"))
    )
    (net (code "3") (name "Net-(AUS-PP)") (class "Default")
      (node (ref "AUS") (pin "TP") (pinfunction "PP_TP") (pintype "input"))
      (node (ref "BA") (pin "P$1") (pinfunction "P_P$1") (pintype "bidirectional"))
      (node (ref "IC2") (pin "7") (pinfunction "OUT_7") (pintype "output"))
      (node (ref "R7") (pin "1") (pinfunction "1_1") (pintype "passive"))
    )
    (net (code "4") (name "Net-(AUS1-PP)") (class "Default")
      (node (ref "AUS1") (pin "TP") (pinfunction "PP_TP") (pintype "input"))
      (node (ref "BA.") (pin "P$1") (pinfunction "P_P$1") (pintype "bidirectional"))
      (node (ref "IC3") (pin "7") (pinfunction "OUT_7") (pintype "output"))
      (node (ref "R10") (pin "1") (pinfunction "1_1") (pintype "passive"))
    )
    (net (code "5") (name "Net-(AUS2-PP)") (class "Default")
      (node (ref "AUS2") (pin "TP") (pinfunction "PP_TP") (pintype "input"))
      (node (ref "BA2") (pin "P$1") (pinfunction "P_P$1") (pintype "bidirectional"))
      (node (ref "IC5") (pin "7") (pinfunction "OUT_7") (pintype "output"))
      (node (ref "R17") (pin "1") (pinfunction "1_1") (pintype "passive"))
    )
    (net (code "6") (name "Net-(AUS3-PP)") (class "Default")
      (node (ref "AUS3") (pin "TP") (pinfunction "PP_TP") (pintype "input"))
      (node (ref "BA3") (pin "P$1") (pinfunction "P_P$1") (pintype "bidirectional"))
      (node (ref "IC7") (pin "7") (pinfunction "OUT_7") (pintype "output"))
      (node (ref "R24") (pin "1") (pinfunction "1_1") (pintype "passive"))
    )
    (net (code "7") (name "Net-(AUS4-PP)") (class "Default")
      (node (ref "AUS4") (pin "TP") (pinfunction "PP_TP") (pintype "input"))
      (node (ref "BA4") (pin "P$1") (pinfunction "P_P$1") (pintype "bidirectional"))
      (node (ref "IC9") (pin "7") (pinfunction "OUT_7") (pintype "output"))
      (node (ref "R31") (pin "1") (pinfunction "1_1") (pintype "passive"))
    )
    (net (code "8") (name "Net-(AUS5-PP)") (class "Default")
      (node (ref "AUS5") (pin "TP") (pinfunction "PP_TP") (pintype "input"))
      (node (ref "BA5") (pin "P$1") (pinfunction "P_P$1") (pintype "bidirectional"))
      (node (ref "IC11") (pin "7") (pinfunction "OUT_7") (pintype "output"))
      (node (ref "R38") (pin "1") (pinfunction "1_1") (pintype "passive"))
    )
    (net (code "9") (name "Net-(AUS6-PP)") (class "Default")
      (node (ref "AUS6") (pin "TP") (pinfunction "PP_TP") (pintype "input"))
      (node (ref "BA6") (pin "P$1") (pinfunction "P_P$1") (pintype "bidirectional"))
      (node (ref "IC13") (pin "7") (pinfunction "OUT_7") (pintype "output"))
      (node (ref "R45") (pin "1") (pinfunction "1_1") (pintype "passive"))
    )
    (net (code "10") (name "Net-(AUS7-PP)") (class "Default")
      (node (ref "AUS7") (pin "TP") (pinfunction "PP_TP") (pintype "input"))
      (node (ref "BA7") (pin "P$1") (pinfunction "P_P$1") (pintype "bidirectional"))
      (node (ref "IC15") (pin "7") (pinfunction "OUT_7") (pintype "output"))
      (node (ref "R52") (pin "1") (pinfunction "1_1") (pintype "passive"))
    )
    (net (code "11") (name "Net-(BE-P)") (class "Default")
      (node (ref "BE") (pin "P$1") (pinfunction "P_P$1") (pintype "bidirectional"))
      (node (ref "EIN") (pin "TP") (pinfunction "PP_TP") (pintype "input"))
      (node (ref "R1") (pin "2") (pinfunction "2_2") (pintype "passive"))
    )
    (net (code "12") (name "Net-(BE.-P)") (class "Default")
      (node (ref "BE.") (pin "P$1") (pinfunction "P_P$1") (pintype "bidirectional"))
      (node (ref "EIN1") (pin "TP") (pinfunction "PP_TP") (pintype "input"))
      (node (ref "R13") (pin "2") (pinfunction "2_2") (pintype "passive"))
    )
    (net (code "13") (name "Net-(BE2-P)") (class "Default")
      (node (ref "BE2") (pin "P$1") (pinfunction "P_P$1") (pintype "bidirectional"))
      (node (ref "EIN2") (pin "TP") (pinfunction "PP_TP") (pintype "input"))
      (node (ref "R20") (pin "2") (pinfunction "2_2") (pintype "passive"))
    )
    (net (code "14") (name "Net-(BE3-P)") (class "Default")
      (node (ref "BE3") (pin "P$1") (pinfunction "P_P$1") (pintype "bidirectional"))
      (node (ref "EIN3") (pin "TP") (pinfunction "PP_TP") (pintype "input"))
      (node (ref "R27") (pin "2") (pinfunction "2_2") (pintype "passive"))
    )
    (net (code "15") (name "Net-(BE4-P)") (class "Default")
      (node (ref "BE4") (pin "P$1") (pinfunction "P_P$1") (pintype "bidirectional"))
      (node (ref "EIN4") (pin "TP") (pinfunction "PP_TP") (pintype "input"))
      (node (ref "R34") (pin "2") (pinfunction "2_2") (pintype "passive"))
    )
    (net (code "16") (name "Net-(BE5-P)") (class "Default")
      (node (ref "BE5") (pin "P$1") (pinfunction "P_P$1") (pintype "bidirectional"))
      (node (ref "EIN5") (pin "TP") (pinfunction "PP_TP") (pintype "input"))
      (node (ref "R41") (pin "2") (pinfunction "2_2") (pintype "passive"))
    )
    (net (code "17") (name "Net-(BE6-P)") (class "Default")
      (node (ref "BE6") (pin "P$1") (pinfunction "P_P$1") (pintype "bidirectional"))
      (node (ref "EIN6") (pin "TP") (pinfunction "PP_TP") (pintype "input"))
      (node (ref "R48") (pin "2") (pinfunction "2_2") (pintype "passive"))
    )
    (net (code "18") (name "Net-(BE7-P)") (class "Default")
      (node (ref "BE7") (pin "P$1") (pinfunction "P_P$1") (pintype "bidirectional"))
      (node (ref "EIN7") (pin "TP") (pinfunction "PP_TP") (pintype "input"))
      (node (ref "R55") (pin "2") (pinfunction "2_2") (pintype "passive"))
    )
    (net (code "19") (name "Net-(C2-Pad1)") (class "Default")
      (node (ref "C2") (pin "1") (pinfunction "1_1") (pintype "passive"))
      (node (ref "R3") (pin "1") (pinfunction "1_1") (pintype "passive"))
      (node (ref "R4") (pin "1") (pinfunction "1_1") (pintype "passive"))
    )
    (net (code "20") (name "Net-(C5-Pad1)") (class "Default")
      (node (ref "C5") (pin "1") (pinfunction "1_1") (pintype "passive"))
      (node (ref "R8") (pin "1") (pinfunction "1_1") (pintype "passive"))
      (node (ref "R9") (pin "1") (pinfunction "1_1") (pintype "passive"))
    )
    (net (code "21") (name "Net-(C8-Pad1)") (class "Default")
      (node (ref "C8") (pin "1") (pinfunction "1_1") (pintype "passive"))
      (node (ref "R15") (pin "1") (pinfunction "1_1") (pintype "passive"))
      (node (ref "R16") (pin "1") (pinfunction "1_1") (pintype "passive"))
    )
    (net (code "22") (name "Net-(C11-Pad1)") (class "Default")
      (node (ref "C11") (pin "1") (pinfunction "1_1") (pintype "passive"))
      (node (ref "R22") (pin "1") (pinfunction "1_1") (pintype "passive"))
      (node (ref "R23") (pin "1") (pinfunction "1_1") (pintype "passive"))
    )
    (net (code "23") (name "Net-(C14-Pad1)") (class "Default")
      (node (ref "C14") (pin "1") (pinfunction "1_1") (pintype "passive"))
      (node (ref "R29") (pin "1") (pinfunction "1_1") (pintype "passive"))
      (node (ref "R30") (pin "1") (pinfunction "1_1") (pintype "passive"))
    )
    (net (code "24") (name "Net-(C17-Pad1)") (class "Default")
      (node (ref "C17") (pin "1") (pinfunction "1_1") (pintype "passive"))
      (node (ref "R36") (pin "1") (pinfunction "1_1") (pintype "passive"))
      (node (ref "R37") (pin "1") (pinfunction "1_1") (pintype "passive"))
    )
    (net (code "25") (name "Net-(C20-Pad1)") (class "Default")
      (node (ref "C20") (pin "1") (pinfunction "1_1") (pintype "passive"))
      (node (ref "R43") (pin "1") (pinfunction "1_1") (pintype "passive"))
      (node (ref "R44") (pin "1") (pinfunction "1_1") (pintype "passive"))
    )
    (net (code "26") (name "Net-(C23-Pad1)") (class "Default")
      (node (ref "C23") (pin "1") (pinfunction "1_1") (pintype "passive"))
      (node (ref "R50") (pin "1") (pinfunction "1_1") (pintype "passive"))
      (node (ref "R51") (pin "1") (pinfunction "1_1") (pintype "passive"))
    )
    (net (code "27") (name "Net-(D1--)") (class "Default")
      (node (ref "D1") (pin "2") (pinfunction "-_2") (pintype "passive"))
      (node (ref "IC1") (pin "3") (pinfunction "IN_3") (pintype "input"))
    )
    (net (code "28") (name "Net-(D2--)") (class "Default")
      (node (ref "D2") (pin "2") (pinfunction "-_2") (pintype "passive"))
      (node (ref "IC2") (pin "5") (pinfunction "+IN_5") (pintype "input"))
      (node (ref "R4") (pin "2") (pinfunction "2_2") (pintype "passive"))
      (node (ref "R7") (pin "2") (pinfunction "2_2") (pintype "passive"))
    )
    (net (code "29") (name "Net-(D3--)") (class "Default")
      (node (ref "D3") (pin "2") (pinfunction "-_2") (pintype "passive"))
      (node (ref "IC4") (pin "3") (pinfunction "IN_3") (pintype "input"))
    )
    (net (code "30") (name "Net-(D4--)") (class "Default")
      (node (ref "D4") (pin "2") (pinfunction "-_2") (pintype "passive"))
      (node (ref "IC3") (pin "5") (pinfunction "+IN_5") (pintype "input"))
      (node (ref "R10") (pin "2") (pinfunction "2_2") (pintype "passive"))
      (node (ref "R9") (pin "2") (pinfunction "2_2") (pintype "passive"))
    )
    (net (code "31") (name "Net-(D5--)") (class "Default")
      (node (ref "D5") (pin "2") (pinfunction "-_2") (pintype "passive"))
      (node (ref "IC6") (pin "3") (pinfunction "IN_3") (pintype "input"))
    )
    (net (code "32") (name "Net-(D6--)") (class "Default")
      (node (ref "D6") (pin "2") (pinfunction "-_2") (pintype "passive"))
      (node (ref "IC5") (pin "5") (pinfunction "+IN_5") (pintype "input"))
      (node (ref "R16") (pin "2") (pinfunction "2_2") (pintype "passive"))
      (node (ref "R17") (pin "2") (pinfunction "2_2") (pintype "passive"))
    )
    (net (code "33") (name "Net-(D7--)") (class "Default")
      (node (ref "D7") (pin "2") (pinfunction "-_2") (pintype "passive"))
      (node (ref "IC8") (pin "3") (pinfunction "IN_3") (pintype "input"))
    )
    (net (code "34") (name "Net-(D8--)") (class "Default")
      (node (ref "D8") (pin "2") (pinfunction "-_2") (pintype "passive"))
      (node (ref "IC7") (pin "5") (pinfunction "+IN_5") (pintype "input"))
      (node (ref "R23") (pin "2") (pinfunction "2_2") (pintype "passive"))
      (node (ref "R24") (pin "2") (pinfunction "2_2") (pintype "passive"))
    )
    (net (code "35") (name "Net-(D9--)") (class "Default")
      (node (ref "D9") (pin "2") (pinfunction "-_2") (pintype "passive"))
      (node (ref "IC10") (pin "3") (pinfunction "IN_3") (pintype "input"))
    )
    (net (code "36") (name "Net-(D10--)") (class "Default")
      (node (ref "D10") (pin "2") (pinfunction "-_2") (pintype "passive"))
      (node (ref "IC9") (pin "5") (pinfunction "+IN_5") (pintype "input"))
      (node (ref "R30") (pin "2") (pinfunction "2_2") (pintype "passive"))
      (node (ref "R31") (pin "2") (pinfunction "2_2") (pintype "passive"))
    )
    (net (code "37") (name "Net-(D11--)") (class "Default")
      (node (ref "D11") (pin "2") (pinfunction "-_2") (pintype "passive"))
      (node (ref "IC12") (pin "3") (pinfunction "IN_3") (pintype "input"))
    )
    (net (code "38") (name "Net-(D12--)") (class "Default")
      (node (ref "D12") (pin "2") (pinfunction "-_2") (pintype "passive"))
      (node (ref "IC11") (pin "5") (pinfunction "+IN_5") (pintype "input"))
      (node (ref "R37") (pin "2") (pinfunction "2_2") (pintype "passive"))
      (node (ref "R38") (pin "2") (pinfunction "2_2") (pintype "passive"))
    )
    (net (code "39") (name "Net-(D13--)") (class "Default")
      (node (ref "D13") (pin "2") (pinfunction "-_2") (pintype "passive"))
      (node (ref "IC14") (pin "3") (pinfunction "IN_3") (pintype "input"))
    )
    (net (code "40") (name "Net-(D14--)") (class "Default")
      (node (ref "D14") (pin "2") (pinfunction "-_2") (pintype "passive"))
      (node (ref "IC13") (pin "5") (pinfunction "+IN_5") (pintype "input"))
      (node (ref "R44") (pin "2") (pinfunction "2_2") (pintype "passive"))
      (node (ref "R45") (pin "2") (pinfunction "2_2") (pintype "passive"))
    )
    (net (code "41") (name "Net-(D15--)") (class "Default")
      (node (ref "D15") (pin "2") (pinfunction "-_2") (pintype "passive"))
      (node (ref "IC16") (pin "3") (pinfunction "IN_3") (pintype "input"))
    )
    (net (code "42") (name "Net-(D16--)") (class "Default")
      (node (ref "D16") (pin "2") (pinfunction "-_2") (pintype "passive"))
      (node (ref "IC15") (pin "5") (pinfunction "+IN_5") (pintype "input"))
      (node (ref "R51") (pin "2") (pinfunction "2_2") (pintype "passive"))
      (node (ref "R52") (pin "2") (pinfunction "2_2") (pintype "passive"))
    )
    (net (code "43") (name "Net-(IC2A-+IN)") (class "Default")
      (node (ref "C1") (pin "1") (pinfunction "1_1") (pintype "passive"))
      (node (ref "IC2") (pin "3") (pinfunction "+IN_3") (pintype "input"))
      (node (ref "R1") (pin "1") (pinfunction "1_1") (pintype "passive"))
    )
    (net (code "44") (name "Net-(IC2A--IN)") (class "Default")
      (node (ref "IC2") (pin "2") (pinfunction "-IN_2") (pintype "input"))
      (node (ref "R2") (pin "2") (pinfunction "2_2") (pintype "passive"))
    )
    (net (code "45") (name "Net-(IC2A-OUT)") (class "Default")
      (node (ref "IC2") (pin "1") (pinfunction "OUT_1") (pintype "output"))
      (node (ref "R3") (pin "2") (pinfunction "2_2") (pintype "passive"))
    )
    (net (code "46") (name "Net-(IC2B--IN)") (class "Default")
      (node (ref "IC2") (pin "6") (pinfunction "-IN_6") (pintype "input"))
      (node (ref "R5") (pin "1") (pinfunction "1_1") (pintype "passive"))
      (node (ref "R6") (pin "2") (pinfunction "2_2") (pintype "passive"))
    )
    (net (code "47") (name "Net-(IC3A-+IN)") (class "Default")
      (node (ref "C6") (pin "1") (pinfunction "1_1") (pintype "passive"))
      (node (ref "IC3") (pin "3") (pinfunction "+IN_3") (pintype "input"))
      (node (ref "R13") (pin "1") (pinfunction "1_1") (pintype "passive"))
    )
    (net (code "48") (name "Net-(IC3A--IN)") (class "Default")
      (node (ref "IC3") (pin "2") (pinfunction "-IN_2") (pintype "input"))
      (node (ref "R14") (pin "2") (pinfunction "2_2") (pintype "passive"))
    )
    (net (code "49") (name "Net-(IC3A-OUT)") (class "Default")
      (node (ref "IC3") (pin "1") (pinfunction "OUT_1") (pintype "output"))
      (node (ref "R8") (pin "2") (pinfunction "2_2") (pintype "passive"))
    )
    (net (code "50") (name "Net-(IC3B--IN)") (class "Default")
      (node (ref "IC3") (pin "6") (pinfunction "-IN_6") (pintype "input"))
      (node (ref "R11") (pin "1") (pinfunction "1_1") (pintype "passive"))
      (node (ref "R12") (pin "2") (pinfunction "2_2") (pintype "passive"))
    )
    (net (code "51") (name "Net-(IC5A-+IN)") (class "Default")
      (node (ref "C9") (pin "1") (pinfunction "1_1") (pintype "passive"))
      (node (ref "IC5") (pin "3") (pinfunction "+IN_3") (pintype "input"))
      (node (ref "R20") (pin "1") (pinfunction "1_1") (pintype "passive"))
    )
    (net (code "52") (name "Net-(IC5A--IN)") (class "Default")
      (node (ref "IC5") (pin "2") (pinfunction "-IN_2") (pintype "input"))
      (node (ref "R21") (pin "2") (pinfunction "2_2") (pintype "passive"))
    )
    (net (code "53") (name "Net-(IC5A-OUT)") (class "Default")
      (node (ref "IC5") (pin "1") (pinfunction "OUT_1") (pintype "output"))
      (node (ref "R15") (pin "2") (pinfunction "2_2") (pintype "passive"))
    )
    (net (code "54") (name "Net-(IC5B--IN)") (class "Default")
      (node (ref "IC5") (pin "6") (pinfunction "-IN_6") (pintype "input"))
      (node (ref "R18") (pin "1") (pinfunction "1_1") (pintype "passive"))
      (node (ref "R19") (pin "2") (pinfunction "2_2") (pintype "passive"))
    )
    (net (code "55") (name "Net-(IC7A-+IN)") (class "Default")
      (node (ref "C12") (pin "1") (pinfunction "1_1") (pintype "passive"))
      (node (ref "IC7") (pin "3") (pinfunction "+IN_3") (pintype "input"))
      (node (ref "R27") (pin "1") (pinfunction "1_1") (pintype "passive"))
    )
    (net (code "56") (name "Net-(IC7A--IN)") (class "Default")
      (node (ref "IC7") (pin "2") (pinfunction "-IN_2") (pintype "input"))
      (node (ref "R28") (pin "2") (pinfunction "2_2") (pintype "passive"))
    )
    (net (code "57") (name "Net-(IC7A-OUT)") (class "Default")
      (node (ref "IC7") (pin "1") (pinfunction "OUT_1") (pintype "output"))
      (node (ref "R22") (pin "2") (pinfunction "2_2") (pintype "passive"))
    )
    (net (code "58") (name "Net-(IC7B--IN)") (class "Default")
      (node (ref "IC7") (pin "6") (pinfunction "-IN_6") (pintype "input"))
      (node (ref "R25") (pin "1") (pinfunction "1_1") (pintype "passive"))
      (node (ref "R26") (pin "2") (pinfunction "2_2") (pintype "passive"))
    )
    (net (code "59") (name "Net-(IC9A-+IN)") (class "Default")
      (node (ref "C15") (pin "1") (pinfunction "1_1") (pintype "passive"))
      (node (ref "IC9") (pin "3") (pinfunction "+IN_3") (pintype "input"))
      (node (ref "R34") (pin "1") (pinfunction "1_1") (pintype "passive"))
    )
    (net (code "60") (name "Net-(IC9A--IN)") (class "Default")
      (node (ref "IC9") (pin "2") (pinfunction "-IN_2") (pintype "input"))
      (node (ref "R35") (pin "2") (pinfunction "2_2") (pintype "passive"))
    )
    (net (code "61") (name "Net-(IC9A-OUT)") (class "Default")
      (node (ref "IC9") (pin "1") (pinfunction "OUT_1") (pintype "output"))
      (node (ref "R29") (pin "2") (pinfunction "2_2") (pintype "passive"))
    )
    (net (code "62") (name "Net-(IC9B--IN)") (class "Default")
      (node (ref "IC9") (pin "6") (pinfunction "-IN_6") (pintype "input"))
      (node (ref "R32") (pin "1") (pinfunction "1_1") (pintype "passive"))
      (node (ref "R33") (pin "2") (pinfunction "2_2") (pintype "passive"))
    )
    (net (code "63") (name "Net-(IC11A-+IN)") (class "Default")
      (node (ref "C18") (pin "1") (pinfunction "1_1") (pintype "passive"))
      (node (ref "IC11") (pin "3") (pinfunction "+IN_3") (pintype "input"))
      (node (ref "R41") (pin "1") (pinfunction "1_1") (pintype "passive"))
    )
    (net (code "64") (name "Net-(IC11A--IN)") (class "Default")
      (node (ref "IC11") (pin "2") (pinfunction "-IN_2") (pintype "input"))
      (node (ref "R42") (pin "2") (pinfunction "2_2") (pintype "passive"))
    )
    (net (code "65") (name "Net-(IC11A-OUT)") (class "Default")
      (node (ref "IC11") (pin "1") (pinfunction "OUT_1") (pintype "output"))
      (node (ref "R36") (pin "2") (pinfunction "2_2") (pintype "passive"))
    )
    (net (code "66") (name "Net-(IC11B--IN)") (class "Default")
      (node (ref "IC11") (pin "6") (pinfunction "-IN_6") (pintype "input"))
      (node (ref "R39") (pin "1") (pinfunction "1_1") (pintype "passive"))
      (node (ref "R40") (pin "2") (pinfunction "2_2") (pintype "passive"))
    )
    (net (code "67") (name "Net-(IC13A-+IN)") (class "Default")
      (node (ref "C21") (pin "1") (pinfunction "1_1") (pintype "passive"))
      (node (ref "IC13") (pin "3") (pinfunction "+IN_3") (pintype "input"))
      (node (ref "R48") (pin "1") (pinfunction "1_1") (pintype "passive"))
    )
    (net (code "68") (name "Net-(IC13A--IN)") (class "Default")
      (node (ref "IC13") (pin "2") (pinfunction "-IN_2") (pintype "input"))
      (node (ref "R49") (pin "2") (pinfunction "2_2") (pintype "passive"))
    )
    (net (code "69") (name "Net-(IC13A-OUT)") (class "Default")
      (node (ref "IC13") (pin "1") (pinfunction "OUT_1") (pintype "output"))
      (node (ref "R43") (pin "2") (pinfunction "2_2") (pintype "passive"))
    )
    (net (code "70") (name "Net-(IC13B--IN)") (class "Default")
      (node (ref "IC13") (pin "6") (pinfunction "-IN_6") (pintype "input"))
      (node (ref "R46") (pin "1") (pinfunction "1_1") (pintype "passive"))
      (node (ref "R47") (pin "2") (pinfunction "2_2") (pintype "passive"))
    )
    (net (code "71") (name "Net-(IC15A-+IN)") (class "Default")
      (node (ref "C24") (pin "1") (pinfunction "1_1") (pintype "passive"))
      (node (ref "IC15") (pin "3") (pinfunction "+IN_3") (pintype "input"))
      (node (ref "R55") (pin "1") (pinfunction "1_1") (pintype "passive"))
    )
    (net (code "72") (name "Net-(IC15A--IN)") (class "Default")
      (node (ref "IC15") (pin "2") (pinfunction "-IN_2") (pintype "input"))
      (node (ref "R56") (pin "2") (pinfunction "2_2") (pintype "passive"))
    )
    (net (code "73") (name "Net-(IC15A-OUT)") (class "Default")
      (node (ref "IC15") (pin "1") (pinfunction "OUT_1") (pintype "output"))
      (node (ref "R50") (pin "2") (pinfunction "2_2") (pintype "passive"))
    )
    (net (code "74") (name "Net-(IC15B--IN)") (class "Default")
      (node (ref "IC15") (pin "6") (pinfunction "-IN_6") (pintype "input"))
      (node (ref "R53") (pin "1") (pinfunction "1_1") (pintype "passive"))
      (node (ref "R54") (pin "2") (pinfunction "2_2") (pintype "passive"))
    )
    (net (code "75") (name "VCC") (class "Default")
      (node (ref "6V") (pin "TP") (pinfunction "PP_TP") (pintype "input"))
      (node (ref "6V1") (pin "TP") (pinfunction "PP_TP") (pintype "input"))
      (node (ref "6V2") (pin "TP") (pinfunction "PP_TP") (pintype "input"))
      (node (ref "6V3") (pin "TP") (pinfunction "PP_TP") (pintype "input"))
      (node (ref "6V4") (pin "TP") (pinfunction "PP_TP") (pintype "input"))
      (node (ref "6V5") (pin "TP") (pinfunction "PP_TP") (pintype "input"))
      (node (ref "6V6") (pin "TP") (pinfunction "PP_TP") (pintype "input"))
      (node (ref "6V7") (pin "TP") (pinfunction "PP_TP") (pintype "input"))
      (node (ref "C10") (pin "1") (pinfunction "1_1") (pintype "passive"))
      (node (ref "C13") (pin "1") (pinfunction "1_1") (pintype "passive"))
      (node (ref "C16") (pin "1") (pinfunction "1_1") (pintype "passive"))
      (node (ref "C19") (pin "1") (pinfunction "1_1") (pintype "passive"))
      (node (ref "C22") (pin "1") (pinfunction "1_1") (pintype "passive"))
      (node (ref "C3") (pin "1") (pinfunction "1_1") (pintype "passive"))
      (node (ref "C4") (pin "1") (pinfunction "1_1") (pintype "passive"))
      (node (ref "C7") (pin "1") (pinfunction "1_1") (pintype "passive"))
      (node (ref "IC1") (pin "1") (pinfunction "OUT_1") (pintype "passive"))
      (node (ref "IC10") (pin "1") (pinfunction "OUT_1") (pintype "passive"))
      (node (ref "IC11") (pin "8") (pinfunction "V+_8") (pintype "power_in"))
      (node (ref "IC12") (pin "1") (pinfunction "OUT_1") (pintype "passive"))
      (node (ref "IC13") (pin "8") (pinfunction "V+_8") (pintype "power_in"))
      (node (ref "IC14") (pin "1") (pinfunction "OUT_1") (pintype "passive"))
      (node (ref "IC15") (pin "8") (pinfunction "V+_8") (pintype "power_in"))
      (node (ref "IC16") (pin "1") (pinfunction "OUT_1") (pintype "passive"))
      (node (ref "IC2") (pin "8") (pinfunction "V+_8") (pintype "power_in"))
      (node (ref "IC3") (pin "8") (pinfunction "V+_8") (pintype "power_in"))
      (node (ref "IC4") (pin "1") (pinfunction "OUT_1") (pintype "passive"))
      (node (ref "IC5") (pin "8") (pinfunction "V+_8") (pintype "power_in"))
      (node (ref "IC6") (pin "1") (pinfunction "OUT_1") (pintype "passive"))
      (node (ref "IC7") (pin "8") (pinfunction "V+_8") (pintype "power_in"))
      (node (ref "IC8") (pin "1") (pinfunction "OUT_1") (pintype "passive"))
      (node (ref "IC9") (pin "8") (pinfunction "V+_8") (pintype "power_in"))
      (node (ref "R11") (pin "2") (pinfunction "2_2") (pintype "passive"))
      (node (ref "R18") (pin "2") (pinfunction "2_2") (pintype "passive"))
      (node (ref "R25") (pin "2") (pinfunction "2_2") (pintype "passive"))
      (node (ref "R32") (pin "2") (pinfunction "2_2") (pintype "passive"))
      (node (ref "R39") (pin "2") (pinfunction "2_2") (pintype "passive"))
      (node (ref "R46") (pin "2") (pinfunction "2_2") (pintype "passive"))
      (node (ref "R5") (pin "2") (pinfunction "2_2") (pintype "passive"))
      (node (ref "R53") (pin "2") (pinfunction "2_2") (pintype "passive"))
    )
  )
)
